# bme_ads1299.net
KiCad netlist of a schematic drawn in Altium Designer
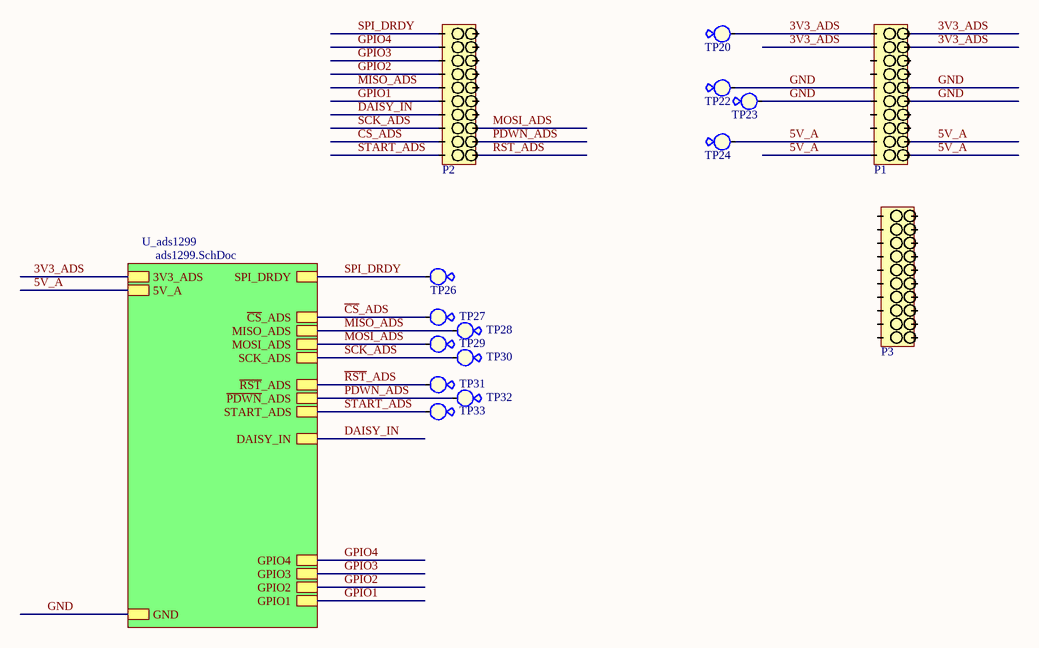
[diagram p0: bme_ads1299.SchDoc]

(export (version "E")
  (design (tool "Eeschema 10.0.6"))
  (components
    (comp (ref "P1")
      (value "Mount Header (Male) 1.27mm")
      (footprint "M50-4301045")
      (description "2x10 Mount Header (Male)")
      (libsource (lib "jclib") (part "2x10 Mount Header (Male) 1.27mm"))
    )
    (comp (ref "P2")
      (value "Mount Header (Male) 1.27mm")
      (footprint "M50-4301045")
      (description "2x10 Mount Header (Male)")
      (libsource (lib "jclib") (part "2x10 Mount Header (Male) 1.27mm"))
    )
    (comp (ref "P3")
      (value "Mount Header (Male) 1.27mm")
      (footprint "M50-4301045")
      (description "2x10 Mount Header (Male)")
      (libsource (lib "jclib") (part "2x10 Mount Header (Male) 1.27mm"))
    )
    (comp (ref "TP20")
      (value "Test Point")
      (footprint "testPoint")
      (libsource (lib "jclib") (part "Test Point"))
    )
    (comp (ref "TP22")
      (value "Test Point")
      (footprint "testPoint")
      (libsource (lib "jclib") (part "Test Point"))
    )
    (comp (ref "TP23")
      (value "Test Point")
      (footprint "testPoint")
      (libsource (lib "jclib") (part "Test Point"))
    )
    (comp (ref "TP24")
      (value "Test Point")
      (footprint "testPoint")
      (libsource (lib "jclib") (part "Test Point"))
    )
    (comp (ref "TP26")
      (value "Test Point")
      (footprint "testPoint")
      (libsource (lib "jclib") (part "Test Point"))
    )
    (comp (ref "TP27")
      (value "Test Point")
      (footprint "testPoint")
      (libsource (lib "jclib") (part "Test Point"))
    )
    (comp (ref "TP28")
      (value "Test Point")
      (footprint "testPoint")
      (libsource (lib "jclib") (part "Test Point"))
    )
    (comp (ref "TP29")
      (value "Test Point")
      (footprint "testPoint")
      (libsource (lib "jclib") (part "Test Point"))
    )
    (comp (ref "TP30")
      (value "Test Point")
      (footprint "testPoint")
      (libsource (lib "jclib") (part "Test Point"))
    )
    (comp (ref "TP31")
      (value "Test Point")
      (footprint "testPoint")
      (libsource (lib "jclib") (part "Test Point"))
    )
    (comp (ref "TP32")
      (value "Test Point")
      (footprint "testPoint")
      (libsource (lib "jclib") (part "Test Point"))
    )
    (comp (ref "TP33")
      (value "Test Point")
      (footprint "testPoint")
      (libsource (lib "jclib") (part "Test Point"))
    )
  )
  (nets
    (net (code "1") (name "/3V3_ADS") (class "Default")
      (node (ref "P1") (pin "1") (pinfunction "1_1") (pintype "passive"))
      (node (ref "P1") (pin "19") (pinfunction "19_19") (pintype "passive"))
      (node (ref "P1") (pin "2") (pinfunction "2_2") (pintype "passive"))
      (node (ref "P1") (pin "20") (pinfunction "20_20") (pintype "passive"))
      (node (ref "TP20") (pin "0") (pinfunction "0_0") (pintype "passive"))
    )
    (net (code "2") (name "/5V_A") (class "Default")
      (node (ref "P1") (pin "10") (pinfunction "10_10") (pintype "passive"))
      (node (ref "P1") (pin "11") (pinfunction "11_11") (pintype "passive"))
      (node (ref "P1") (pin "12") (pinfunction "12_12") (pintype "passive"))
      (node (ref "P1") (pin "9") (pinfunction "9_9") (pintype "passive"))
      (node (ref "TP24") (pin "0") (pinfunction "0_0") (pintype "passive"))
    )
    (net (code "3") (name "/DAISY_IN") (class "Default")
      (node (ref "P2") (pin "7") (pinfunction "7_7") (pintype "passive"))
    )
    (net (code "4") (name "/GND") (class "Default")
      (node (ref "P1") (pin "15") (pinfunction "15_15") (pintype "passive"))
      (node (ref "P1") (pin "16") (pinfunction "16_16") (pintype "passive"))
      (node (ref "P1") (pin "5") (pinfunction "5_5") (pintype "passive"))
      (node (ref "P1") (pin "6") (pinfunction "6_6") (pintype "passive"))
      (node (ref "TP22") (pin "0") (pinfunction "0_0") (pintype "passive"))
      (node (ref "TP23") (pin "0") (pinfunction "0_0") (pintype "passive"))
    )
    (net (code "5") (name "/GPIO1") (class "Default")
      (node (ref "P2") (pin "6") (pinfunction "6_6") (pintype "passive"))
    )
    (net (code "6") (name "/GPIO2") (class "Default")
      (node (ref "P2") (pin "4") (pinfunction "4_4") (pintype "passive"))
    )
    (net (code "7") (name "/GPIO3") (class "Default")
      (node (ref "P2") (pin "3") (pinfunction "3_3") (pintype "passive"))
    )
    (net (code "8") (name "/GPIO4") (class "Default")
      (node (ref "P2") (pin "2") (pinfunction "2_2") (pintype "passive"))
    )
    (net (code "9") (name "/MISO_ADS") (class "Default")
      (node (ref "P2") (pin "5") (pinfunction "5_5") (pintype "passive"))
      (node (ref "TP28") (pin "0") (pinfunction "0_0") (pintype "passive"))
    )
    (net (code "10") (name "/MOSI_ADS") (class "Default")
      (node (ref "P2") (pin "13") (pinfunction "13_13") (pintype "passive"))
      (node (ref "TP29") (pin "0") (pinfunction "0_0") (pintype "passive"))
    )
    (net (code "11") (name "/SCK_ADS") (class "Default")
      (node (ref "P2") (pin "8") (pinfunction "8_8") (pintype "passive"))
      (node (ref "TP30") (pin "0") (pinfunction "0_0") (pintype "passive"))
    )
    (net (code "12") (name "/SPI_DRDY") (class "Default")
      (node (ref "P2") (pin "1") (pinfunction "1_1") (pintype "passive"))
      (node (ref "TP26") (pin "0") (pinfunction "0_0") (pintype "passive"))
    )
    (net (code "13") (name "/START_ADS") (class "Default")
      (node (ref "P2") (pin "10") (pinfunction "10_10") (pintype "passive"))
      (node (ref "TP33") (pin "0") (pinfunction "0_0") (pintype "passive"))
    )
    (net (code "14") (name "/~{CS}_ADS") (class "Default")
      (node (ref "P2") (pin "9") (pinfunction "9_9") (pintype "passive"))
      (node (ref "TP27") (pin "0") (pinfunction "0_0") (pintype "passive"))
    )
    (net (code "15") (name "/~{PDWN}_ADS") (class "Default")
      (node (ref "P2") (pin "12") (pinfunction "12_12") (pintype "passive"))
      (node (ref "TP32") (pin "0") (pinfunction "0_0") (pintype "passive"))
    )
    (net (code "16") (name "/~{RST}_ADS") (class "Default")
      (node (ref "P2") (pin "11") (pinfunction "11_11") (pintype "passive"))
      (node (ref "TP31") (pin "0") (pinfunction "0_0") (pintype "passive"))
    )
    (net (code "17") (name "unconnected-(P1-Pad3)") (class "Default")
      (node (ref "P1") (pin "3") (pinfunction "3_3") (pintype "passive"))
    )
    (net (code "18") (name "unconnected-(P1-Pad4)") (class "Default")
      (node (ref "P1") (pin "4") (pinfunction "4_4") (pintype "passive"))
    )
    (net (code "19") (name "unconnected-(P1-Pad7)") (class "Default")
      (node (ref "P1") (pin "7") (pinfunction "7_7") (pintype "passive"))
    )
    (net (code "20") (name "unconnected-(P1-Pad8)") (class "Default")
      (node (ref "P1") (pin "8") (pinfunction "8_8") (pintype "passive"))
    )
    (net (code "21") (name "unconnected-(P1-Pad13)") (class "Default")
      (node (ref "P1") (pin "13") (pinfunction "13_13") (pintype "passive"))
    )
    (net (code "22") (name "unconnected-(P1-Pad14)") (class "Default")
      (node (ref "P1") (pin "14") (pinfunction "14_14") (pintype "passive"))
    )
    (net (code "23") (name "unconnected-(P1-Pad17)") (class "Default")
      (node (ref "P1") (pin "17") (pinfunction "17_17") (pintype "passive"))
    )
    (net (code "24") (name "unconnected-(P1-Pad18)") (class "Default")
      (node (ref "P1") (pin "18") (pinfunction "18_18") (pintype "passive"))
    )
    (net (code "25") (name "unconnected-(P2-Pad14)") (class "Default")
      (node (ref "P2") (pin "14") (pinfunction "14_14") (pintype "passive"))
    )
    (net (code "26") (name "unconnected-(P2-Pad15)") (class "Default")
      (node (ref "P2") (pin "15") (pinfunction "15_15") (pintype "passive"))
    )
    (net (code "27") (name "unconnected-(P2-Pad16)") (class "Default")
      (node (ref "P2") (pin "16") (pinfunction "16_16") (pintype "passive"))
    )
    (net (code "28") (name "unconnected-(P2-Pad17)") (class "Default")
      (node (ref "P2") (pin "17") (pinfunction "17_17") (pintype "passive"))
    )
    (net (code "29") (name "unconnected-(P2-Pad18)") (class "Default")
      (node (ref "P2") (pin "18") (pinfunction "18_18") (pintype "passive"))
    )
    (net (code "30") (name "unconnected-(P2-Pad19)") (class "Default")
      (node (ref "P2") (pin "19") (pinfunction "19_19") (pintype "passive"))
    )
    (net (code "31") (name "unconnected-(P2-Pad20)") (class "Default")
      (node (ref "P2") (pin "20") (pinfunction "20_20") (pintype "passive"))
    )
    (net (code "32") (name "unconnected-(P3-Pad1)") (class "Default")
      (node (ref "P3") (pin "1") (pinfunction "1_1") (pintype "passive"))
    )
    (net (code "33") (name "unconnected-(P3-Pad2)") (class "Default")
      (node (ref "P3") (pin "2") (pinfunction "2_2") (pintype "passive"))
    )
    (net (code "34") (name "unconnected-(P3-Pad3)") (class "Default")
      (node (ref "P3") (pin "3") (pinfunction "3_3") (pintype "passive"))
    )
    (net (code "35") (name "unconnected-(P3-Pad4)") (class "Default")
      (node (ref "P3") (pin "4") (pinfunction "4_4") (pintype "passive"))
    )
    (net (code "36") (name "unconnected-(P3-Pad5)") (class "Default")
      (node (ref "P3") (pin "5") (pinfunction "5_5") (pintype "passive"))
    )
    (net (code "37") (name "unconnected-(P3-Pad6)") (class "Default")
      (node (ref "P3") (pin "6") (pinfunction "6_6") (pintype "passive"))
    )
    (net (code "38") (name "unconnected-(P3-Pad7)") (class "Default")
      (node (ref "P3") (pin "7") (pinfunction "7_7") (pintype "passive"))
    )
    (net (code "39") (name "unconnected-(P3-Pad8)") (class "Default")
      (node (ref "P3") (pin "8") (pinfunction "8_8") (pintype "passive"))
    )
    (net (code "40") (name "unconnected-(P3-Pad9)") (class "Default")
      (node (ref "P3") (pin "9") (pinfunction "9_9") (pintype "passive"))
    )
    (net (code "41") (name "unconnected-(P3-Pad10)") (class "Default")
      (node (ref "P3") (pin "10") (pinfunction "10_10") (pintype "passive"))
    )
    (net (code "42") (name "unconnected-(P3-Pad11)") (class "Default")
      (node (ref "P3") (pin "11") (pinfunction "11_11") (pintype "passive"))
    )
    (net (code "43") (name "unconnected-(P3-Pad12)") (class "Default")
      (node (ref "P3") (pin "12") (pinfunction "12_12") (pintype "passive"))
    )
    (net (code "44") (name "unconnected-(P3-Pad13)") (class "Default")
      (node (ref "P3") (pin "13") (pinfunction "13_13") (pintype "passive"))
    )
    (net (code "45") (name "unconnected-(P3-Pad14)") (class "Default")
      (node (ref "P3") (pin "14") (pinfunction "14_14") (pintype "passive"))
    )
    (net (code "46") (name "unconnected-(P3-Pad15)") (class "Default")
      (node (ref "P3") (pin "15") (pinfunction "15_15") (pintype "passive"))
    )
    (net (code "47") (name "unconnected-(P3-Pad16)") (class "Default")
      (node (ref "P3") (pin "16") (pinfunction "16_16") (pintype "passive"))
    )
    (net (code "48") (name "unconnected-(P3-Pad17)") (class "Default")
      (node (ref "P3") (pin "17") (pinfunction "17_17") (pintype "passive"))
    )
    (net (code "49") (name "unconnected-(P3-Pad18)") (class "Default")
      (node (ref "P3") (pin "18") (pinfunction "18_18") (pintype "passive"))
    )
    (net (code "50") (name "unconnected-(P3-Pad19)") (class "Default")
      (node (ref "P3") (pin "19") (pinfunction "19_19") (pintype "passive"))
    )
    (net (code "51") (name "unconnected-(P3-Pad20)") (class "Default")
      (node (ref "P3") (pin "20") (pinfunction "20_20") (pintype "passive"))
    )
  )
)
